# domus-silicea-board01-schematic.net
KiCad netlist of a schematic drawn in EAGLE
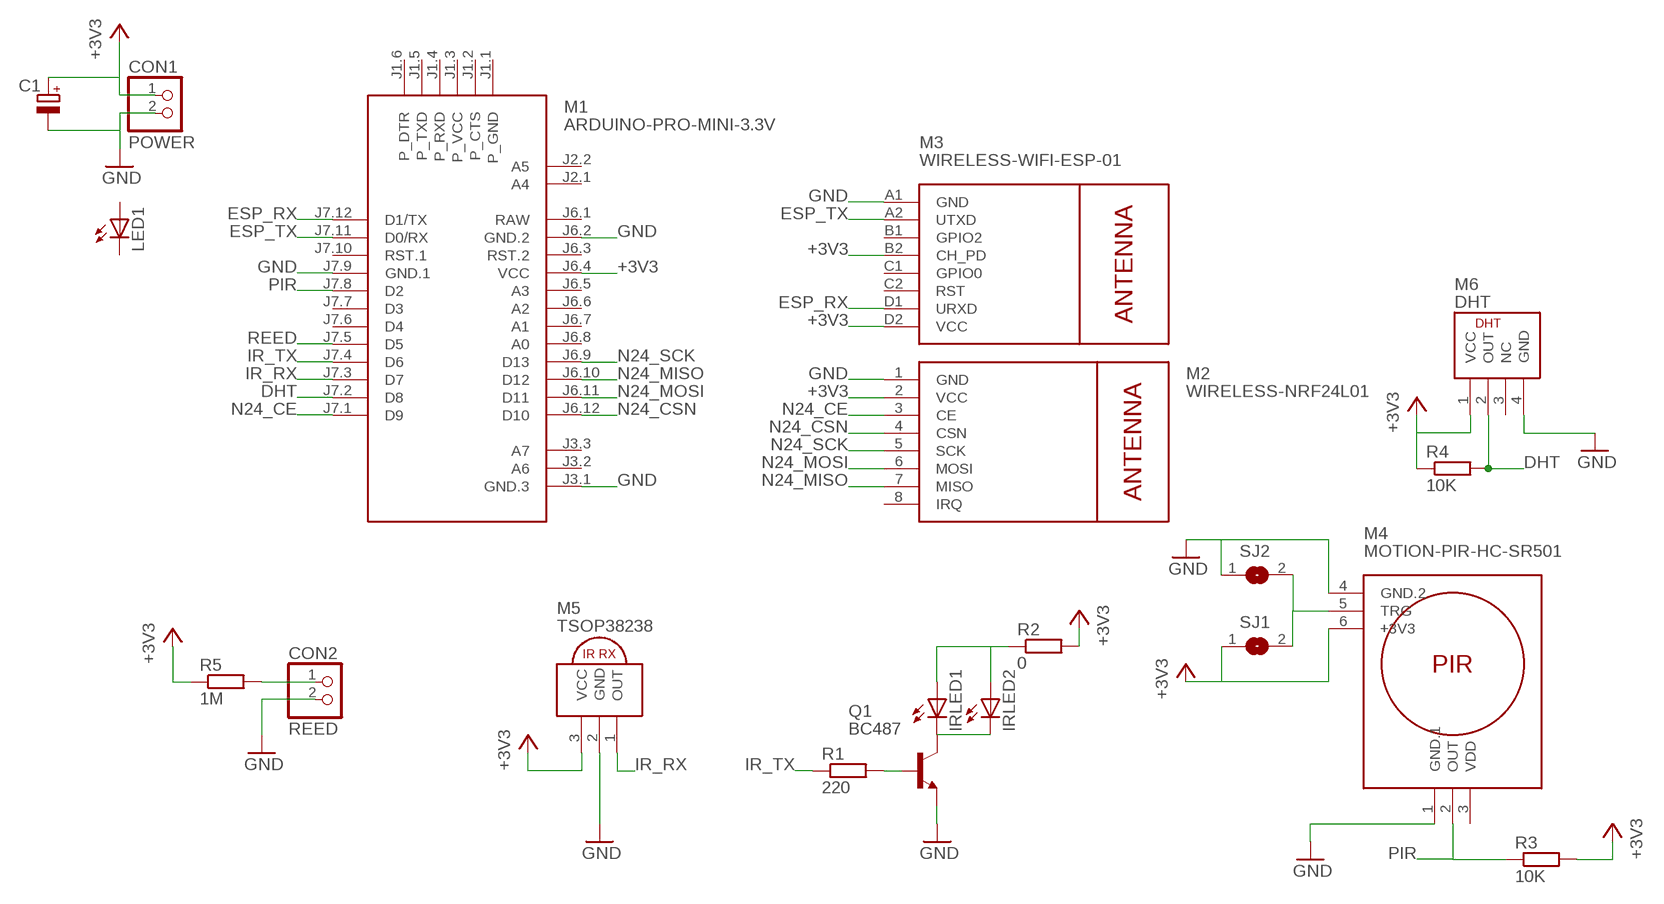
[diagram p0: schematic, sheet 1]

(export (version "E")
  (design (tool "Eeschema 10.0.6"))
  (components
    (comp (ref "C1")
      (value "CPOL-EUE2,5-6E")
      (footprint "eagle-import:E2,5-6E")
      (libsource (lib "eagle-import") (part "CPOL-EUE2,5-6E"))
    )
    (comp (ref "CON1")
      (value "POWER")
      (footprint "eagle-import:1X02")
      (libsource (lib "eagle-import") (part "PINHD-1X2"))
    )
    (comp (ref "CON2")
      (value "REED")
      (footprint "eagle-import:1X02")
      (libsource (lib "eagle-import") (part "PINHD-1X2"))
    )
    (comp (ref "IRLED1")
      (value "LED5MM")
      (footprint "eagle-import:LED5MM")
      (libsource (lib "eagle-import") (part "LED5MM"))
    )
    (comp (ref "IRLED2")
      (value "LED5MM")
      (footprint "eagle-import:LED5MM")
      (libsource (lib "eagle-import") (part "LED5MM"))
    )
    (comp (ref "LED1")
      (value "LED5MM")
      (footprint "eagle-import:LED5MM")
      (libsource (lib "eagle-import") (part "LED5MM"))
    )
    (comp (ref "M1")
      (value "ARDUINO-PRO-MINI-3.3V")
      (footprint "eagle-import:ARDUINO-PRO-MINI")
      (libsource (lib "eagle-import") (part "ARDUINO-PRO-MINI-3.3V"))
    )
    (comp (ref "M2")
      (value "WIRELESS-NRF24L01")
      (footprint "eagle-import:WIRELESS-NRF24L01")
      (libsource (lib "eagle-import") (part "WIRELESS-NRF24L01"))
    )
    (comp (ref "M3")
      (value "WIRELESS-WIFI-ESP-01")
      (footprint "eagle-import:WIRELESS-WIFI-ESP-01")
      (libsource (lib "eagle-import") (part "WIRELESS-WIFI-ESP-01"))
    )
    (comp (ref "M4")
      (value "MOTION-PIR-HC-SR501")
      (footprint "eagle-import:MOTION-PIR-HC-SR501")
      (libsource (lib "eagle-import") (part "MOTION-PIR-HC-SR501"))
    )
    (comp (ref "M5")
      (value "TSOP38238")
      (footprint "eagle-import:TSOP38238")
      (libsource (lib "eagle-import") (part "TSOP38238"))
    )
    (comp (ref "M6")
      (value "DHT")
      (footprint "eagle-import:DHT")
      (libsource (lib "eagle-import") (part "DHT"))
    )
    (comp (ref "Q1")
      (value "BC487")
      (footprint "eagle-import:TO92-EBC")
      (libsource (lib "eagle-import") (part "BC487"))
    )
    (comp (ref "R1")
      (value "220")
      (footprint "eagle-import:0207_10")
      (libsource (lib "eagle-import") (part "R-EU_0207/10"))
    )
    (comp (ref "R2")
      (value "0")
      (footprint "eagle-import:0207_10")
      (libsource (lib "eagle-import") (part "R-EU_0207/10"))
    )
    (comp (ref "R3")
      (value "10K")
      (footprint "eagle-import:0207_10")
      (libsource (lib "eagle-import") (part "R-EU_0207/10"))
    )
    (comp (ref "R4")
      (value "10K")
      (footprint "eagle-import:0207_10")
      (libsource (lib "eagle-import") (part "R-EU_0207/10"))
    )
    (comp (ref "R5")
      (value "1M")
      (footprint "eagle-import:0207_10")
      (libsource (lib "eagle-import") (part "R-EU_0207/10"))
    )
    (comp (ref "SJ1") (value "SJ") (footprint "eagle-import:SJ") (libsource (lib "eagle-import") (part "SJ")))
    (comp (ref "SJ2") (value "SJ") (footprint "eagle-import:SJ") (libsource (lib "eagle-import") (part "SJ")))
  )
  (nets
    (net (code "1") (name "+3V3") (class "Default")
      (node (ref "C1") (pin "+") (pinfunction "+_+") (pintype "passive"))
      (node (ref "CON1") (pin "1") (pinfunction "1_1") (pintype "passive"))
      (node (ref "M1") (pin "J6.4") (pinfunction "VCC_J6.4") (pintype "power_in"))
      (node (ref "M2") (pin "2") (pinfunction "VCC_2") (pintype "power_in"))
      (node (ref "M3") (pin "B2") (pinfunction "CH_PD_B2") (pintype "bidirectional"))
      (node (ref "M3") (pin "D2") (pinfunction "VCC_D2") (pintype "power_in"))
      (node (ref "M4") (pin "6") (pinfunction "+3V3_6") (pintype "power_in"))
      (node (ref "M5") (pin "3") (pinfunction "VCC_3") (pintype "power_in"))
      (node (ref "M6") (pin "1") (pinfunction "VCC_1") (pintype "power_in"))
      (node (ref "R2") (pin "2") (pinfunction "2_2") (pintype "passive"))
      (node (ref "R3") (pin "2") (pinfunction "2_2") (pintype "passive"))
      (node (ref "R4") (pin "1") (pinfunction "1_1") (pintype "passive"))
      (node (ref "R5") (pin "1") (pinfunction "1_1") (pintype "passive"))
      (node (ref "SJ1") (pin "1") (pinfunction "1_1") (pintype "passive"))
    )
    (net (code "2") (name "/DHT") (class "Default")
      (node (ref "M1") (pin "J7.2") (pinfunction "D8_J7.2") (pintype "bidirectional"))
      (node (ref "M6") (pin "2") (pinfunction "OUT_2") (pintype "output"))
      (node (ref "R4") (pin "2") (pinfunction "2_2") (pintype "passive"))
    )
    (net (code "3") (name "/ESP_RX") (class "Default")
      (node (ref "M1") (pin "J7.12") (pinfunction "D1/TX_J7.12") (pintype "bidirectional"))
      (node (ref "M3") (pin "D1") (pinfunction "URXD_D1") (pintype "bidirectional"))
    )
    (net (code "4") (name "/ESP_TX") (class "Default")
      (node (ref "M1") (pin "J7.11") (pinfunction "D0/RX_J7.11") (pintype "bidirectional"))
      (node (ref "M3") (pin "A2") (pinfunction "UTXD_A2") (pintype "bidirectional"))
    )
    (net (code "5") (name "/IR_RX") (class "Default")
      (node (ref "M1") (pin "J7.3") (pinfunction "D7_J7.3") (pintype "bidirectional"))
      (node (ref "M5") (pin "1") (pinfunction "OUT_1") (pintype "output"))
    )
    (net (code "6") (name "/IR_TX") (class "Default")
      (node (ref "M1") (pin "J7.4") (pinfunction "D6_J7.4") (pintype "bidirectional"))
      (node (ref "R1") (pin "1") (pinfunction "1_1") (pintype "passive"))
    )
    (net (code "7") (name "/N24_CE") (class "Default")
      (node (ref "M1") (pin "J7.1") (pinfunction "D9_J7.1") (pintype "bidirectional"))
      (node (ref "M2") (pin "3") (pinfunction "CE_3") (pintype "bidirectional"))
    )
    (net (code "8") (name "/N24_CSN") (class "Default")
      (node (ref "M1") (pin "J6.12") (pinfunction "D10_J6.12") (pintype "bidirectional"))
      (node (ref "M2") (pin "4") (pinfunction "CSN_4") (pintype "bidirectional"))
    )
    (net (code "9") (name "/N24_MISO") (class "Default")
      (node (ref "M1") (pin "J6.10") (pinfunction "D12_J6.10") (pintype "bidirectional"))
      (node (ref "M2") (pin "7") (pinfunction "MISO_7") (pintype "bidirectional"))
    )
    (net (code "10") (name "/N24_MOSI") (class "Default")
      (node (ref "M1") (pin "J6.11") (pinfunction "D11_J6.11") (pintype "bidirectional"))
      (node (ref "M2") (pin "6") (pinfunction "MOSI_6") (pintype "bidirectional"))
    )
    (net (code "11") (name "/N24_SCK") (class "Default")
      (node (ref "M1") (pin "J6.9") (pinfunction "D13_J6.9") (pintype "bidirectional"))
      (node (ref "M2") (pin "5") (pinfunction "SCK_5") (pintype "bidirectional"))
    )
    (net (code "12") (name "/PIR") (class "Default")
      (node (ref "M1") (pin "J7.8") (pinfunction "D2_J7.8") (pintype "bidirectional"))
      (node (ref "M4") (pin "2") (pinfunction "OUT_2") (pintype "output"))
      (node (ref "R3") (pin "1") (pinfunction "1_1") (pintype "passive"))
    )
    (net (code "13") (name "/RAW") (class "Default")
      (node (ref "M1") (pin "J6.1") (pinfunction "RAW_J6.1") (pintype "power_in"))
    )
    (net (code "14") (name "/REED") (class "Default")
      (node (ref "M1") (pin "J7.5") (pinfunction "D5_J7.5") (pintype "bidirectional"))
    )
    (net (code "15") (name "/VDD") (class "Default")
      (node (ref "M4") (pin "3") (pinfunction "VDD_3") (pintype "power_in"))
    )
    (net (code "16") (name "GND") (class "Default")
      (node (ref "C1") (pin "-") (pinfunction "-_-") (pintype "passive"))
      (node (ref "CON1") (pin "2") (pinfunction "2_2") (pintype "passive"))
      (node (ref "CON2") (pin "2") (pinfunction "2_2") (pintype "passive"))
      (node (ref "M1") (pin "J3.1") (pinfunction "GND.3_J3.1") (pintype "bidirectional"))
      (node (ref "M1") (pin "J6.2") (pinfunction "GND.2_J6.2") (pintype "power_in"))
      (node (ref "M1") (pin "J7.9") (pinfunction "GND.1_J7.9") (pintype "power_in"))
      (node (ref "M2") (pin "1") (pinfunction "GND_1") (pintype "power_in"))
      (node (ref "M3") (pin "A1") (pinfunction "GND_A1") (pintype "power_in"))
      (node (ref "M4") (pin "1") (pinfunction "GND.1_1") (pintype "power_in"))
      (node (ref "M4") (pin "4") (pinfunction "GND.2_4") (pintype "power_in"))
      (node (ref "M5") (pin "2") (pinfunction "GND_2") (pintype "power_in"))
      (node (ref "M6") (pin "4") (pinfunction "GND_4") (pintype "power_in"))
      (node (ref "Q1") (pin "E") (pinfunction "E_E") (pintype "passive"))
      (node (ref "SJ2") (pin "1") (pinfunction "1_1") (pintype "passive"))
    )
    (net (code "17") (name "Net-(CON2-Pad1)") (class "Default")
      (node (ref "CON2") (pin "1") (pinfunction "1_1") (pintype "passive"))
      (node (ref "R5") (pin "2") (pinfunction "2_2") (pintype "passive"))
    )
    (net (code "18") (name "Net-(IRLED1-C)") (class "Default")
      (node (ref "IRLED1") (pin "K") (pinfunction "C_K") (pintype "passive"))
      (node (ref "IRLED2") (pin "K") (pinfunction "C_K") (pintype "passive"))
      (node (ref "Q1") (pin "C") (pinfunction "C_C") (pintype "passive"))
    )
    (net (code "19") (name "Net-(IRLED1-PadA)") (class "Default")
      (node (ref "IRLED1") (pin "A") (pinfunction "A_A") (pintype "passive"))
      (node (ref "IRLED2") (pin "A") (pinfunction "A_A") (pintype "passive"))
      (node (ref "R2") (pin "1") (pinfunction "1_1") (pintype "passive"))
    )
    (net (code "20") (name "Net-(M4-TRG)") (class "Default")
      (node (ref "M4") (pin "5") (pinfunction "TRG_5") (pintype "input"))
      (node (ref "SJ1") (pin "2") (pinfunction "2_2") (pintype "passive"))
      (node (ref "SJ2") (pin "2") (pinfunction "2_2") (pintype "passive"))
    )
    (net (code "21") (name "Net-(Q1-PadB)") (class "Default")
      (node (ref "Q1") (pin "B") (pinfunction "B_B") (pintype "passive"))
      (node (ref "R1") (pin "2") (pinfunction "2_2") (pintype "passive"))
    )
    (net (code "22") (name "unconnected-(LED1-C-PadK)") (class "Default")
      (node (ref "LED1") (pin "K") (pinfunction "C_K") (pintype "passive"))
    )
    (net (code "23") (name "unconnected-(LED1-PadA)") (class "Default")
      (node (ref "LED1") (pin "A") (pinfunction "A_A") (pintype "passive"))
    )
    (net (code "24") (name "unconnected-(M1-A0-PadJ6.8)") (class "Default")
      (node (ref "M1") (pin "J6.8") (pinfunction "A0_J6.8") (pintype "bidirectional"))
    )
    (net (code "25") (name "unconnected-(M1-A1-PadJ6.7)") (class "Default")
      (node (ref "M1") (pin "J6.7") (pinfunction "A1_J6.7") (pintype "bidirectional"))
    )
    (net (code "26") (name "unconnected-(M1-A2-PadJ6.6)") (class "Default")
      (node (ref "M1") (pin "J6.6") (pinfunction "A2_J6.6") (pintype "bidirectional"))
    )
    (net (code "27") (name "unconnected-(M1-A3-PadJ6.5)") (class "Default")
      (node (ref "M1") (pin "J6.5") (pinfunction "A3_J6.5") (pintype "bidirectional"))
    )
    (net (code "28") (name "unconnected-(M1-A4-PadJ2.1)") (class "Default")
      (node (ref "M1") (pin "J2.1") (pinfunction "A4_J2.1") (pintype "bidirectional"))
    )
    (net (code "29") (name "unconnected-(M1-A5-PadJ2.2)") (class "Default")
      (node (ref "M1") (pin "J2.2") (pinfunction "A5_J2.2") (pintype "bidirectional"))
    )
    (net (code "30") (name "unconnected-(M1-A6-PadJ3.2)") (class "Default")
      (node (ref "M1") (pin "J3.2") (pinfunction "A6_J3.2") (pintype "bidirectional"))
    )
    (net (code "31") (name "unconnected-(M1-A7-PadJ3.3)") (class "Default")
      (node (ref "M1") (pin "J3.3") (pinfunction "A7_J3.3") (pintype "bidirectional"))
    )
    (net (code "32") (name "unconnected-(M1-D3-PadJ7.7)") (class "Default")
      (node (ref "M1") (pin "J7.7") (pinfunction "D3_J7.7") (pintype "bidirectional"))
    )
    (net (code "33") (name "unconnected-(M1-D4-PadJ7.6)") (class "Default")
      (node (ref "M1") (pin "J7.6") (pinfunction "D4_J7.6") (pintype "bidirectional"))
    )
    (net (code "34") (name "unconnected-(M1-P_CTS-PadJ1.2)") (class "Default")
      (node (ref "M1") (pin "J1.2") (pinfunction "P_CTS_J1.2") (pintype "bidirectional"))
    )
    (net (code "35") (name "unconnected-(M1-P_DTR-PadJ1.6)") (class "Default")
      (node (ref "M1") (pin "J1.6") (pinfunction "P_DTR_J1.6") (pintype "bidirectional"))
    )
    (net (code "36") (name "unconnected-(M1-P_GND-PadJ1.1)") (class "Default")
      (node (ref "M1") (pin "J1.1") (pinfunction "P_GND_J1.1") (pintype "bidirectional"))
    )
    (net (code "37") (name "unconnected-(M1-P_RXD-PadJ1.4)") (class "Default")
      (node (ref "M1") (pin "J1.4") (pinfunction "P_RXD_J1.4") (pintype "bidirectional"))
    )
    (net (code "38") (name "unconnected-(M1-P_TXD-PadJ1.5)") (class "Default")
      (node (ref "M1") (pin "J1.5") (pinfunction "P_TXD_J1.5") (pintype "bidirectional"))
    )
    (net (code "39") (name "unconnected-(M1-P_VCC-PadJ1.3)") (class "Default")
      (node (ref "M1") (pin "J1.3") (pinfunction "P_VCC_J1.3") (pintype "bidirectional"))
    )
    (net (code "40") (name "unconnected-(M1-RST.1-PadJ7.10)") (class "Default")
      (node (ref "M1") (pin "J7.10") (pinfunction "RST.1_J7.10") (pintype "bidirectional"))
    )
    (net (code "41") (name "unconnected-(M1-RST.2-PadJ6.3)") (class "Default")
      (node (ref "M1") (pin "J6.3") (pinfunction "RST.2_J6.3") (pintype "bidirectional"))
    )
    (net (code "42") (name "unconnected-(M2-IRQ-Pad8)") (class "Default")
      (node (ref "M2") (pin "8") (pinfunction "IRQ_8") (pintype "bidirectional"))
    )
    (net (code "43") (name "unconnected-(M3-GPIO0-PadC1)") (class "Default")
      (node (ref "M3") (pin "C1") (pinfunction "GPIO0_C1") (pintype "bidirectional"))
    )
    (net (code "44") (name "unconnected-(M3-GPIO2-PadB1)") (class "Default")
      (node (ref "M3") (pin "B1") (pinfunction "GPIO2_B1") (pintype "bidirectional"))
    )
    (net (code "45") (name "unconnected-(M3-RST-PadC2)") (class "Default")
      (node (ref "M3") (pin "C2") (pinfunction "RST_C2") (pintype "bidirectional"))
    )
    (net (code "46") (name "unconnected-(M6-NC-Pad3)") (class "Default")
      (node (ref "M6") (pin "3") (pinfunction "NC_3") (pintype "output"))
    )
  )
)
